# Top.net
KiCad netlist of a schematic drawn in Altium Designer
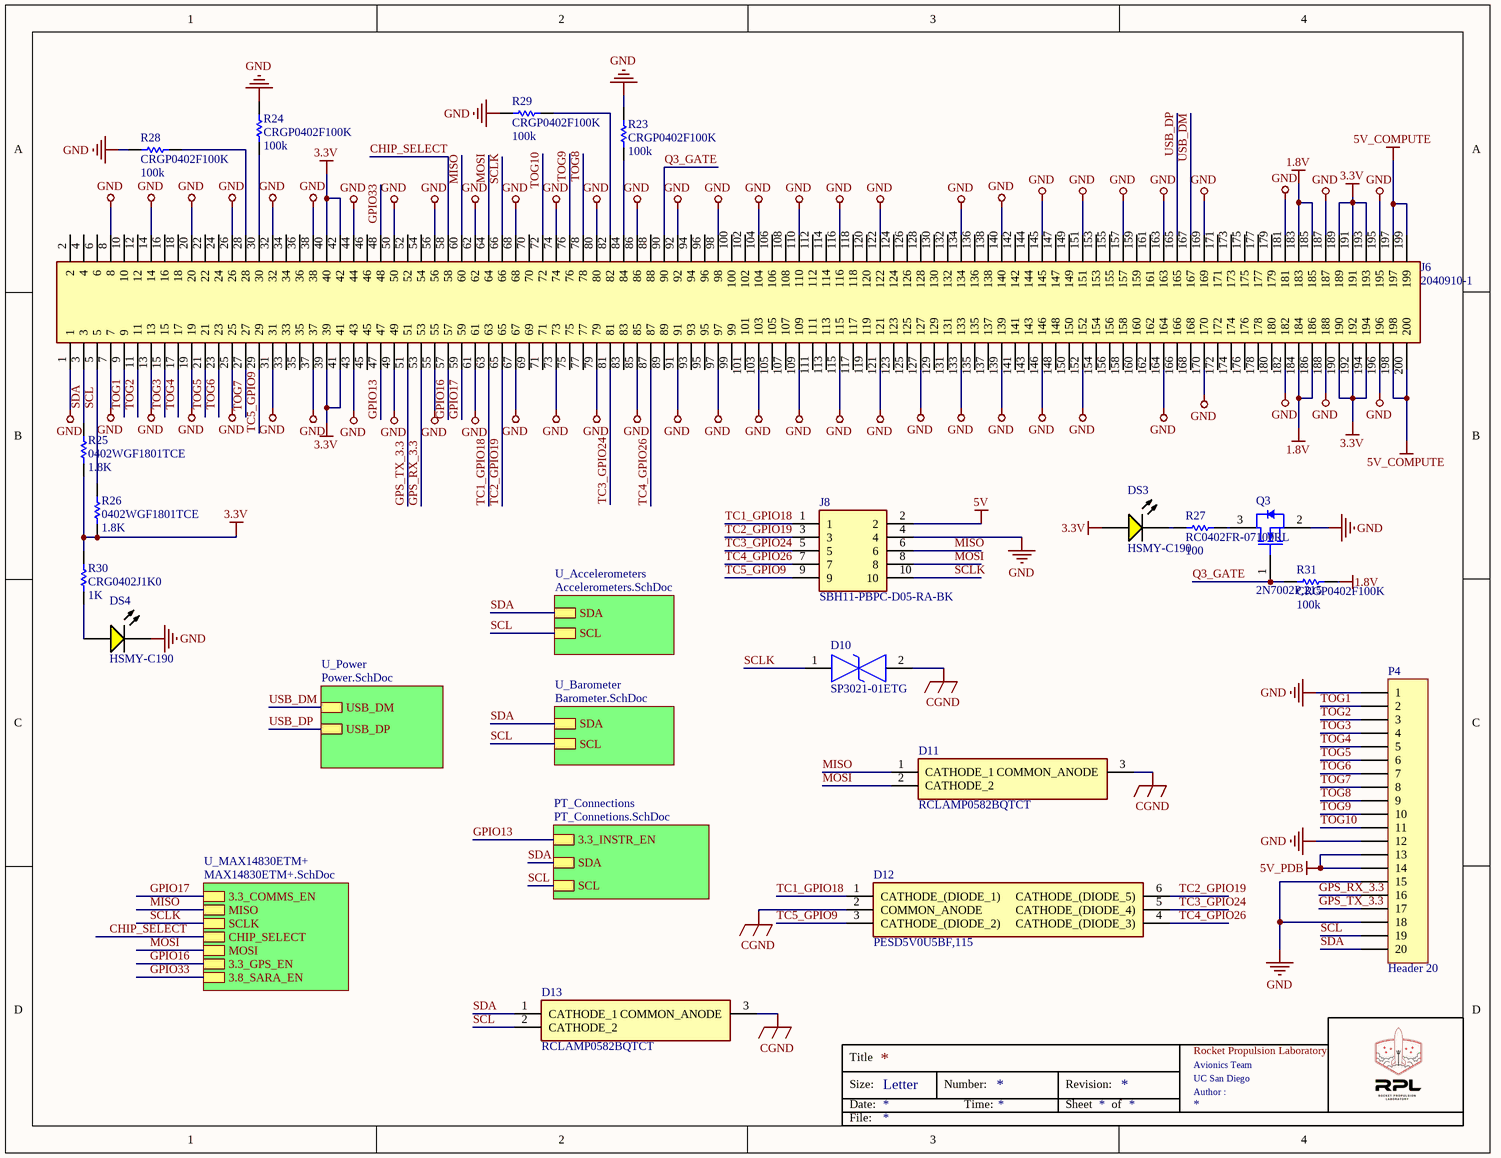
[diagram p0: Top.SchDoc]

(export (version "E")
  (design (tool "Eeschema 10.0.6"))
  (components
    (comp (ref "D10")
      (value "SP3021-01ETG")
      (footprint "PcbLib1:SP302101ETG")
      (description "TVS Diode (Bi-directional)")
      (fields (field (name "MOUSER PART NUMBER") "576-SP3021-01ETG"))
      (libsource (lib "*") (part "SP3021-01ETG"))
    )
    (comp (ref "D11")
      (value "RCLAMP0582BQTCT")
      (footprint "PcbLib1:SOT50P160X90-3N")
      (description "TVS Diode (Uni-directional)")
      (fields (field (name "MOUSER PART NUMBER") "947-RCLAMP0582BQTCT"))
      (libsource (lib "*") (part "RCLAMP0582BQTCT"))
    )
    (comp (ref "D12")
      (value "PESD5V0U5BF,115")
      (footprint "PcbLib1:PESD5V0U5BF115")
      (description "TVS Diode (Uni-directional)")
      (fields (field (name "MOUSER PART NUMBER") "771-PESD5V0U5BF,115"))
      (libsource (lib "*") (part "PESD5V0U5BF,115"))
    )
    (comp (ref "D13")
      (value "RCLAMP0582BQTCT")
      (footprint "PcbLib1:SOT50P160X90-3N")
      (description "TVS Diode (Uni-directional)")
      (fields (field (name "MOUSER PART NUMBER") "947-RCLAMP0582BQTCT"))
      (libsource (lib "*") (part "RCLAMP0582BQTCT"))
    )
    (comp (ref "DS3")
      (value "HSMY-C190")
      (footprint "AVAG-HSMX-C190_V")
      (description "LED Uni-Color Yellow, 65 mW, 20 mA, -40 to 85 degC, 2-Pin SMD, RoHS, Tape and Reel")
      (fields (field (name "TOLERANCE") "1%"))
      (libsource (lib "Altium Content Vault") (part "LED-YELLOW-AK-2"))
    )
    (comp (ref "DS4")
      (value "HSMY-C190")
      (footprint "AVAG-HSMX-C190_V")
      (description "LED Uni-Color Yellow, 65 mW, 20 mA, -40 to 85 degC, 2-Pin SMD, RoHS, Tape and Reel")
      (fields (field (name "TOLERANCE") "1%"))
      (libsource (lib "Altium Content Vault") (part "LED-YELLOW-AK-2"))
    )
    (comp (ref "J6")
      (value "2040910-1")
      (footprint "PcbLib1:20409101")
      (description "Connector")
      (fields (field (name "MOUSER PART NUMBER") "571-2040910-1"))
      (libsource (lib "*") (part "2040910-1"))
    )
    (comp (ref "J8")
      (value "SBH11-PBPC-D05-RA-BK")
      (footprint "PcbLib1:SHDRRA10W64P254_2X5_1270X910X880P")
      (description "Connector")
      (libsource (lib "*") (part "SBH11-PBPC-D05-RA-BK"))
    )
    (comp (ref "P4")
      (value "Header 20")
      (footprint "HDR1X20")
      (description "Header, 20-Pin")
      (fields (field (name "PUBLISHER") "Altium Limited"))
      (libsource (lib "Miscellaneous Connectors") (part "Header 20"))
    )
    (comp (ref "Q3")
      (value "2N7002P,215")
      (footprint "NXP-SOT23_L")
      (description "N-Channel Trench MOSFET, 60 V, 0.36 A, -55 to 150 degC, 3-Pin SOT23, Tape and Reel")
      (fields (field (name "MANUFACTURER") "NXP Semiconductors"))
      (libsource (lib "Altium Content Vault") (part "NXP-NMOS-GSD-3_B"))
    )
    (comp (ref "R23")
      (value "CRGP0402F100K")
      (footprint "0402")
      (description "Resistor")
      (fields (field (name "ALTIUM_VALUE") "100k") (field (name "PUBLISHER") "Altium Limited"))
      (libsource (lib "Miscellaneous Devices") (part "Res1"))
    )
    (comp (ref "R24")
      (value "CRGP0402F100K")
      (footprint "0402")
      (description "Resistor")
      (fields (field (name "ALTIUM_VALUE") "100k") (field (name "PUBLISHER") "Altium Limited"))
      (libsource (lib "Miscellaneous Devices") (part "Res1"))
    )
    (comp (ref "R25")
      (value "0402WGF1801TCE")
      (footprint "0402")
      (description "Resistor")
      (fields (field (name "ALTIUM_VALUE") "1.8K") (field (name "PUBLISHER") "Altium Limited"))
      (libsource (lib "Miscellaneous Devices") (part "Res1"))
    )
    (comp (ref "R26")
      (value "0402WGF1801TCE")
      (footprint "0402")
      (description "Resistor")
      (fields (field (name "ALTIUM_VALUE") "1.8K") (field (name "PUBLISHER") "Altium Limited"))
      (libsource (lib "Miscellaneous Devices") (part "Res1"))
    )
    (comp (ref "R27")
      (value "RC0402FR-07100RL")
      (footprint "RESC1005X40X25ML05T10")
      (fields (field (name "MANUFACTURER") "Yageo / Phycomp") (field (name "SPEC") "100"))
      (libsource (lib "Altium Content Vault") (part "RES"))
    )
    (comp (ref "R28")
      (value "CRGP0402F100K")
      (footprint "0402")
      (description "Resistor")
      (fields (field (name "ALTIUM_VALUE") "100k") (field (name "PUBLISHER") "Altium Limited"))
      (libsource (lib "Miscellaneous Devices") (part "Res1"))
    )
    (comp (ref "R29")
      (value "CRGP0402F100K")
      (footprint "0402")
      (description "Resistor")
      (fields (field (name "ALTIUM_VALUE") "100k") (field (name "PUBLISHER") "Altium Limited"))
      (libsource (lib "Miscellaneous Devices") (part "Res1"))
    )
    (comp (ref "R30")
      (value "CRG0402J1K0")
      (footprint "0402")
      (description "Resistor")
      (fields (field (name "ALTIUM_VALUE") "1K") (field (name "PUBLISHER") "Altium Limited"))
      (libsource (lib "Miscellaneous Devices") (part "Res1"))
    )
    (comp (ref "R31")
      (value "CRGP0402F100K")
      (footprint "0402")
      (description "Resistor")
      (fields (field (name "ALTIUM_VALUE") "100k") (field (name "PUBLISHER") "Altium Limited"))
      (libsource (lib "Miscellaneous Devices") (part "Res1"))
    )
  )
  (nets
    (net (code "1") (name "/CHIP_SELECT") (class "Default")
      (node (ref "J6") (pin "58") (pinfunction "58_58") (pintype "passive"))
    )
    (net (code "2") (name "/GPIO13") (class "Default")
      (node (ref "J6") (pin "47") (pinfunction "47_47") (pintype "passive"))
    )
    (net (code "3") (name "/GPIO16") (class "Default")
      (node (ref "J6") (pin "57") (pinfunction "57_57") (pintype "passive"))
    )
    (net (code "4") (name "/GPIO17") (class "Default")
      (node (ref "J6") (pin "59") (pinfunction "59_59") (pintype "passive"))
    )
    (net (code "5") (name "/GPIO33") (class "Default")
      (node (ref "J6") (pin "48") (pinfunction "48_48") (pintype "passive"))
    )
    (net (code "6") (name "/GPS_RX_3.3") (class "Default")
      (node (ref "J6") (pin "53") (pinfunction "53_53") (pintype "passive"))
      (node (ref "P4") (pin "16") (pinfunction "16_16") (pintype "passive"))
    )
    (net (code "7") (name "/GPS_TX_3.3") (class "Default")
      (node (ref "J6") (pin "51") (pinfunction "51_51") (pintype "passive"))
      (node (ref "P4") (pin "17") (pinfunction "17_17") (pintype "passive"))
    )
    (net (code "8") (name "/MISO") (class "Default")
      (node (ref "D11") (pin "1") (pinfunction "CATHODE_1_1") (pintype "passive"))
      (node (ref "J6") (pin "60") (pinfunction "60_60") (pintype "passive"))
      (node (ref "J8") (pin "6") (pinfunction "6_6") (pintype "passive"))
    )
    (net (code "9") (name "/MOSI") (class "Default")
      (node (ref "D11") (pin "2") (pinfunction "CATHODE_2_2") (pintype "passive"))
      (node (ref "J6") (pin "64") (pinfunction "64_64") (pintype "passive"))
      (node (ref "J8") (pin "8") (pinfunction "8_8") (pintype "passive"))
    )
    (net (code "10") (name "/Q3_GATE") (class "Default")
      (node (ref "J6") (pin "90") (pinfunction "90_90") (pintype "passive"))
      (node (ref "Q3") (pin "1") (pinfunction "G_1") (pintype "passive"))
      (node (ref "R31") (pin "1") (pinfunction "1_1") (pintype "passive"))
    )
    (net (code "11") (name "/SCL") (class "Default")
      (node (ref "D13") (pin "2") (pinfunction "CATHODE_2_2") (pintype "passive"))
      (node (ref "J6") (pin "5") (pinfunction "5_5") (pintype "passive"))
      (node (ref "P4") (pin "19") (pinfunction "19_19") (pintype "passive"))
      (node (ref "R26") (pin "2") (pinfunction "2_2") (pintype "passive"))
    )
    (net (code "12") (name "/SCLK") (class "Default")
      (node (ref "D10") (pin "1") (pinfunction "1_1") (pintype "passive"))
      (node (ref "J6") (pin "66") (pinfunction "66_66") (pintype "passive"))
      (node (ref "J8") (pin "10") (pinfunction "10_10") (pintype "passive"))
    )
    (net (code "13") (name "/SDA") (class "Default")
      (node (ref "D13") (pin "1") (pinfunction "CATHODE_1_1") (pintype "passive"))
      (node (ref "J6") (pin "3") (pinfunction "3_3") (pintype "passive"))
      (node (ref "P4") (pin "20") (pinfunction "20_20") (pintype "passive"))
      (node (ref "R25") (pin "2") (pinfunction "2_2") (pintype "passive"))
    )
    (net (code "14") (name "/TC1_GPIO18") (class "Default")
      (node (ref "D12") (pin "1") (pinfunction "CATHODE_(DIODE_1)_1") (pintype "passive"))
      (node (ref "J6") (pin "63") (pinfunction "63_63") (pintype "passive"))
      (node (ref "J8") (pin "1") (pinfunction "1_1") (pintype "passive"))
    )
    (net (code "15") (name "/TC2_GPIO19") (class "Default")
      (node (ref "D12") (pin "6") (pinfunction "CATHODE_(DIODE_5)_6") (pintype "passive"))
      (node (ref "J6") (pin "65") (pinfunction "65_65") (pintype "passive"))
      (node (ref "J8") (pin "3") (pinfunction "3_3") (pintype "passive"))
    )
    (net (code "16") (name "/TC3_GPIO24") (class "Default")
      (node (ref "D12") (pin "5") (pinfunction "CATHODE_(DIODE_4)_5") (pintype "passive"))
      (node (ref "J6") (pin "81") (pinfunction "81_81") (pintype "passive"))
      (node (ref "J8") (pin "5") (pinfunction "5_5") (pintype "passive"))
    )
    (net (code "17") (name "/TC4_GPIO26") (class "Default")
      (node (ref "D12") (pin "4") (pinfunction "CATHODE_(DIODE_3)_4") (pintype "passive"))
      (node (ref "J6") (pin "87") (pinfunction "87_87") (pintype "passive"))
      (node (ref "J8") (pin "7") (pinfunction "7_7") (pintype "passive"))
    )
    (net (code "18") (name "/TC5_GPIO9") (class "Default")
      (node (ref "D12") (pin "3") (pinfunction "CATHODE_(DIODE_2)_3") (pintype "passive"))
      (node (ref "J6") (pin "29") (pinfunction "29_29") (pintype "passive"))
      (node (ref "J8") (pin "9") (pinfunction "9_9") (pintype "passive"))
    )
    (net (code "19") (name "/TOG1") (class "Default")
      (node (ref "J6") (pin "9") (pinfunction "9_9") (pintype "passive"))
      (node (ref "P4") (pin "2") (pinfunction "2_2") (pintype "passive"))
    )
    (net (code "20") (name "/TOG2") (class "Default")
      (node (ref "J6") (pin "11") (pinfunction "11_11") (pintype "passive"))
      (node (ref "P4") (pin "3") (pinfunction "3_3") (pintype "passive"))
    )
    (net (code "21") (name "/TOG3") (class "Default")
      (node (ref "J6") (pin "15") (pinfunction "15_15") (pintype "passive"))
      (node (ref "P4") (pin "4") (pinfunction "4_4") (pintype "passive"))
    )
    (net (code "22") (name "/TOG4") (class "Default")
      (node (ref "J6") (pin "17") (pinfunction "17_17") (pintype "passive"))
      (node (ref "P4") (pin "5") (pinfunction "5_5") (pintype "passive"))
    )
    (net (code "23") (name "/TOG5") (class "Default")
      (node (ref "J6") (pin "21") (pinfunction "21_21") (pintype "passive"))
      (node (ref "P4") (pin "6") (pinfunction "6_6") (pintype "passive"))
    )
    (net (code "24") (name "/TOG6") (class "Default")
      (node (ref "J6") (pin "23") (pinfunction "23_23") (pintype "passive"))
      (node (ref "P4") (pin "7") (pinfunction "7_7") (pintype "passive"))
    )
    (net (code "25") (name "/TOG7") (class "Default")
      (node (ref "J6") (pin "27") (pinfunction "27_27") (pintype "passive"))
      (node (ref "P4") (pin "8") (pinfunction "8_8") (pintype "passive"))
    )
    (net (code "26") (name "/TOG8") (class "Default")
      (node (ref "J6") (pin "78") (pinfunction "78_78") (pintype "passive"))
      (node (ref "P4") (pin "9") (pinfunction "9_9") (pintype "passive"))
    )
    (net (code "27") (name "/TOG9") (class "Default")
      (node (ref "J6") (pin "76") (pinfunction "76_76") (pintype "passive"))
      (node (ref "P4") (pin "10") (pinfunction "10_10") (pintype "passive"))
    )
    (net (code "28") (name "/TOG10") (class "Default")
      (node (ref "J6") (pin "72") (pinfunction "72_72") (pintype "passive"))
      (node (ref "P4") (pin "11") (pinfunction "11_11") (pintype "passive"))
    )
    (net (code "29") (name "/USB_DM") (class "Default")
      (node (ref "J6") (pin "167") (pinfunction "167_167") (pintype "passive"))
    )
    (net (code "30") (name "/USB_DP") (class "Default")
      (node (ref "J6") (pin "165") (pinfunction "165_165") (pintype "passive"))
    )
    (net (code "31") (name "1.8V") (class "Default")
      (node (ref "J6") (pin "183") (pinfunction "183_183") (pintype "passive"))
      (node (ref "J6") (pin "184") (pinfunction "184_184") (pintype "passive"))
      (node (ref "J6") (pin "185") (pinfunction "185_185") (pintype "passive"))
      (node (ref "J6") (pin "186") (pinfunction "186_186") (pintype "passive"))
      (node (ref "R31") (pin "2") (pinfunction "2_2") (pintype "passive"))
    )
    (net (code "32") (name "3.3V") (class "Default")
      (node (ref "DS3") (pin "1") (pinfunction "A_1") (pintype "passive"))
      (node (ref "J6") (pin "189") (pinfunction "189_189") (pintype "passive"))
      (node (ref "J6") (pin "190") (pinfunction "190_190") (pintype "passive"))
      (node (ref "J6") (pin "191") (pinfunction "191_191") (pintype "passive"))
      (node (ref "J6") (pin "192") (pinfunction "192_192") (pintype "passive"))
      (node (ref "J6") (pin "193") (pinfunction "193_193") (pintype "passive"))
      (node (ref "J6") (pin "194") (pinfunction "194_194") (pintype "passive"))
      (node (ref "J6") (pin "39") (pinfunction "39_39") (pintype "passive"))
      (node (ref "J6") (pin "40") (pinfunction "40_40") (pintype "passive"))
      (node (ref "J6") (pin "41") (pinfunction "41_41") (pintype "passive"))
      (node (ref "J6") (pin "42") (pinfunction "42_42") (pintype "passive"))
      (node (ref "R25") (pin "1") (pinfunction "1_1") (pintype "passive"))
      (node (ref "R26") (pin "1") (pinfunction "1_1") (pintype "passive"))
      (node (ref "R30") (pin "1") (pinfunction "1_1") (pintype "passive"))
    )
    (net (code "33") (name "5V") (class "Default")
      (node (ref "J8") (pin "2") (pinfunction "2_2") (pintype "passive"))
    )
    (net (code "34") (name "5V_COMPUTE") (class "Default")
      (node (ref "J6") (pin "197") (pinfunction "197_197") (pintype "passive"))
      (node (ref "J6") (pin "198") (pinfunction "198_198") (pintype "passive"))
      (node (ref "J6") (pin "199") (pinfunction "199_199") (pintype "passive"))
      (node (ref "J6") (pin "200") (pinfunction "200_200") (pintype "passive"))
    )
    (net (code "35") (name "5V_PDB") (class "Default")
      (node (ref "P4") (pin "13") (pinfunction "13_13") (pintype "passive"))
      (node (ref "P4") (pin "14") (pinfunction "14_14") (pintype "passive"))
    )
    (net (code "36") (name "CGND") (class "Default")
      (node (ref "D10") (pin "2") (pinfunction "2_2") (pintype "passive"))
      (node (ref "D11") (pin "3") (pinfunction "COMMON_ANODE_3") (pintype "passive"))
      (node (ref "D12") (pin "2") (pinfunction "COMMON_ANODE_2") (pintype "passive"))
      (node (ref "D13") (pin "3") (pinfunction "COMMON_ANODE_3") (pintype "passive"))
    )
    (net (code "37") (name "GND") (class "Default")
      (node (ref "DS4") (pin "2") (pinfunction "K_2") (pintype "passive"))
      (node (ref "J6") (pin "1") (pinfunction "1_1") (pintype "passive"))
      (node (ref "J6") (pin "103") (pinfunction "103_103") (pintype "passive"))
      (node (ref "J6") (pin "104") (pinfunction "104_104") (pintype "passive"))
      (node (ref "J6") (pin "109") (pinfunction "109_109") (pintype "passive"))
      (node (ref "J6") (pin "110") (pinfunction "110_110") (pintype "passive"))
      (node (ref "J6") (pin "115") (pinfunction "115_115") (pintype "passive"))
      (node (ref "J6") (pin "116") (pinfunction "116_116") (pintype "passive"))
      (node (ref "J6") (pin "121") (pinfunction "121_121") (pintype "passive"))
      (node (ref "J6") (pin "122") (pinfunction "122_122") (pintype "passive"))
      (node (ref "J6") (pin "127") (pinfunction "127_127") (pintype "passive"))
      (node (ref "J6") (pin "13") (pinfunction "13_13") (pintype "passive"))
      (node (ref "J6") (pin "133") (pinfunction "133_133") (pintype "passive"))
      (node (ref "J6") (pin "134") (pinfunction "134_134") (pintype "passive"))
      (node (ref "J6") (pin "139") (pinfunction "139_139") (pintype "passive"))
      (node (ref "J6") (pin "14") (pinfunction "14_14") (pintype "passive"))
      (node (ref "J6") (pin "140") (pinfunction "140_140") (pintype "passive"))
      (node (ref "J6") (pin "145") (pinfunction "145_145") (pintype "passive"))
      (node (ref "J6") (pin "146") (pinfunction "146_146") (pintype "passive"))
      (node (ref "J6") (pin "151") (pinfunction "151_151") (pintype "passive"))
      (node (ref "J6") (pin "152") (pinfunction "152_152") (pintype "passive"))
      (node (ref "J6") (pin "157") (pinfunction "157_157") (pintype "passive"))
      (node (ref "J6") (pin "163") (pinfunction "163_163") (pintype "passive"))
      (node (ref "J6") (pin "164") (pinfunction "164_164") (pintype "passive"))
      (node (ref "J6") (pin "169") (pinfunction "169_169") (pintype "passive"))
      (node (ref "J6") (pin "170") (pinfunction "170_170") (pintype "passive"))
      (node (ref "J6") (pin "181") (pinfunction "181_181") (pintype "passive"))
      (node (ref "J6") (pin "182") (pinfunction "182_182") (pintype "passive"))
      (node (ref "J6") (pin "187") (pinfunction "187_187") (pintype "passive"))
      (node (ref "J6") (pin "188") (pinfunction "188_188") (pintype "passive"))
      (node (ref "J6") (pin "19") (pinfunction "19_19") (pintype "passive"))
      (node (ref "J6") (pin "195") (pinfunction "195_195") (pintype "passive"))
      (node (ref "J6") (pin "196") (pinfunction "196_196") (pintype "passive"))
      (node (ref "J6") (pin "20") (pinfunction "20_20") (pintype "passive"))
      (node (ref "J6") (pin "25") (pinfunction "25_25") (pintype "passive"))
      (node (ref "J6") (pin "26") (pinfunction "26_26") (pintype "passive"))
      (node (ref "J6") (pin "31") (pinfunction "31_31") (pintype "passive"))
      (node (ref "J6") (pin "32") (pinfunction "32_32") (pintype "passive"))
      (node (ref "J6") (pin "37") (pinfunction "37_37") (pintype "passive"))
      (node (ref "J6") (pin "38") (pinfunction "38_38") (pintype "passive"))
      (node (ref "J6") (pin "43") (pinfunction "43_43") (pintype "passive"))
      (node (ref "J6") (pin "44") (pinfunction "44_44") (pintype "passive"))
      (node (ref "J6") (pin "49") (pinfunction "49_49") (pintype "passive"))
      (node (ref "J6") (pin "50") (pinfunction "50_50") (pintype "passive"))
      (node (ref "J6") (pin "55") (pinfunction "55_55") (pintype "passive"))
      (node (ref "J6") (pin "56") (pinfunction "56_56") (pintype "passive"))
      (node (ref "J6") (pin "61") (pinfunction "61_61") (pintype "passive"))
      (node (ref "J6") (pin "62") (pinfunction "62_62") (pintype "passive"))
      (node (ref "J6") (pin "67") (pinfunction "67_67") (pintype "passive"))
      (node (ref "J6") (pin "68") (pinfunction "68_68") (pintype "passive"))
      (node (ref "J6") (pin "7") (pinfunction "7_7") (pintype "passive"))
      (node (ref "J6") (pin "73") (pinfunction "73_73") (pintype "passive"))
      (node (ref "J6") (pin "74") (pinfunction "74_74") (pintype "passive"))
      (node (ref "J6") (pin "79") (pinfunction "79_79") (pintype "passive"))
      (node (ref "J6") (pin "8") (pinfunction "8_8") (pintype "passive"))
      (node (ref "J6") (pin "80") (pinfunction "80_80") (pintype "passive"))
      (node (ref "J6") (pin "85") (pinfunction "85_85") (pintype "passive"))
      (node (ref "J6") (pin "86") (pinfunction "86_86") (pintype "passive"))
      (node (ref "J6") (pin "91") (pinfunction "91_91") (pintype "passive"))
      (node (ref "J6") (pin "92") (pinfunction "92_92") (pintype "passive"))
      (node (ref "J6") (pin "97") (pinfunction "97_97") (pintype "passive"))
      (node (ref "J6") (pin "98") (pinfunction "98_98") (pintype "passive"))
      (node (ref "J8") (pin "4") (pinfunction "4_4") (pintype "passive"))
      (node (ref "P4") (pin "1") (pinfunction "1_1") (pintype "passive"))
      (node (ref "P4") (pin "12") (pinfunction "12_12") (pintype "passive"))
      (node (ref "P4") (pin "15") (pinfunction "15_15") (pintype "passive"))
      (node (ref "P4") (pin "18") (pinfunction "18_18") (pintype "passive"))
      (node (ref "Q3") (pin "2") (pinfunction "S_2") (pintype "passive"))
      (node (ref "R23") (pin "2") (pinfunction "2_2") (pintype "passive"))
      (node (ref "R24") (pin "2") (pinfunction "2_2") (pintype "passive"))
      (node (ref "R28") (pin "2") (pinfunction "2_2") (pintype "passive"))
      (node (ref "R29") (pin "2") (pinfunction "2_2") (pintype "passive"))
    )
    (net (code "38") (name "Net-(DS3-K)") (class "Default")
      (node (ref "DS3") (pin "2") (pinfunction "K_2") (pintype "passive"))
      (node (ref "R27") (pin "2") (pinfunction "2_2") (pintype "passive"))
    )
    (net (code "39") (name "Net-(DS4-A)") (class "Default")
      (node (ref "DS4") (pin "1") (pinfunction "A_1") (pintype "passive"))
      (node (ref "R30") (pin "2") (pinfunction "2_2") (pintype "passive"))
    )
    (net (code "40") (name "Net-(J6-Pad28)") (class "Default")
      (node (ref "J6") (pin "28") (pinfunction "28_28") (pintype "passive"))
      (node (ref "R28") (pin "1") (pinfunction "1_1") (pintype "passive"))
    )
    (net (code "41") (name "Net-(J6-Pad30)") (class "Default")
      (node (ref "J6") (pin "30") (pinfunction "30_30") (pintype "passive"))
      (node (ref "R24") (pin "1") (pinfunction "1_1") (pintype "passive"))
    )
    (net (code "42") (name "Net-(J6-Pad82)") (class "Default")
      (node (ref "J6") (pin "82") (pinfunction "82_82") (pintype "passive"))
      (node (ref "R29") (pin "1") (pinfunction "1_1") (pintype "passive"))
    )
    (net (code "43") (name "Net-(J6-Pad84)") (class "Default")
      (node (ref "J6") (pin "84") (pinfunction "84_84") (pintype "passive"))
      (node (ref "R23") (pin "1") (pinfunction "1_1") (pintype "passive"))
    )
    (net (code "44") (name "Net-(Q3-D)") (class "Default")
      (node (ref "Q3") (pin "3") (pinfunction "D_3") (pintype "passive"))
      (node (ref "R27") (pin "1") (pinfunction "1_1") (pintype "passive"))
    )
    (net (code "45") (name "unconnected-(J6-Pad2)") (class "Default")
      (node (ref "J6") (pin "2") (pinfunction "2_2") (pintype "passive"))
    )
    (net (code "46") (name "unconnected-(J6-Pad4)") (class "Default")
      (node (ref "J6") (pin "4") (pinfunction "4_4") (pintype "passive"))
    )
    (net (code "47") (name "unconnected-(J6-Pad6)") (class "Default")
      (node (ref "J6") (pin "6") (pinfunction "6_6") (pintype "passive"))
    )
    (net (code "48") (name "unconnected-(J6-Pad10)") (class "Default")
      (node (ref "J6") (pin "10") (pinfunction "10_10") (pintype "passive"))
    )
    (net (code "49") (name "unconnected-(J6-Pad12)") (class "Default")
      (node (ref "J6") (pin "12") (pinfunction "12_12") (pintype "passive"))
    )
    (net (code "50") (name "unconnected-(J6-Pad16)") (class "Default")
      (node (ref "J6") (pin "16") (pinfunction "16_16") (pintype "passive"))
    )
    (net (code "51") (name "unconnected-(J6-Pad18)") (class "Default")
      (node (ref "J6") (pin "18") (pinfunction "18_18") (pintype "passive"))
    )
    (net (code "52") (name "unconnected-(J6-Pad22)") (class "Default")
      (node (ref "J6") (pin "22") (pinfunction "22_22") (pintype "passive"))
    )
    (net (code "53") (name "unconnected-(J6-Pad24)") (class "Default")
      (node (ref "J6") (pin "24") (pinfunction "24_24") (pintype "passive"))
    )
    (net (code "54") (name "unconnected-(J6-Pad33)") (class "Default")
      (node (ref "J6") (pin "33") (pinfunction "33_33") (pintype "passive"))
    )
    (net (code "55") (name "unconnected-(J6-Pad34)") (class "Default")
      (node (ref "J6") (pin "34") (pinfunction "34_34") (pintype "passive"))
    )
    (net (code "56") (name "unconnected-(J6-Pad35)") (class "Default")
      (node (ref "J6") (pin "35") (pinfunction "35_35") (pintype "passive"))
    )
    (net (code "57") (name "unconnected-(J6-Pad36)") (class "Default")
      (node (ref "J6") (pin "36") (pinfunction "36_36") (pintype "passive"))
    )
    (net (code "58") (name "unconnected-(J6-Pad45)") (class "Default")
      (node (ref "J6") (pin "45") (pinfunction "45_45") (pintype "passive"))
    )
    (net (code "59") (name "unconnected-(J6-Pad46)") (class "Default")
      (node (ref "J6") (pin "46") (pinfunction "46_46") (pintype "passive"))
    )
    (net (code "60") (name "unconnected-(J6-Pad52)") (class "Default")
      (node (ref "J6") (pin "52") (pinfunction "52_52") (pintype "passive"))
    )
    (net (code "61") (name "unconnected-(J6-Pad54)") (class "Default")
      (node (ref "J6") (pin "54") (pinfunction "54_54") (pintype "passive"))
    )
    (net (code "62") (name "unconnected-(J6-Pad69)") (class "Default")
      (node (ref "J6") (pin "69") (pinfunction "69_69") (pintype "passive"))
    )
    (net (code "63") (name "unconnected-(J6-Pad70)") (class "Default")
      (node (ref "J6") (pin "70") (pinfunction "70_70") (pintype "passive"))
    )
    (net (code "64") (name "unconnected-(J6-Pad71)") (class "Default")
      (node (ref "J6") (pin "71") (pinfunction "71_71") (pintype "passive"))
    )
    (net (code "65") (name "unconnected-(J6-Pad75)") (class "Default")
      (node (ref "J6") (pin "75") (pinfunction "75_75") (pintype "passive"))
    )
    (net (code "66") (name "unconnected-(J6-Pad77)") (class "Default")
      (node (ref "J6") (pin "77") (pinfunction "77_77") (pintype "passive"))
    )
    (net (code "67") (name "unconnected-(J6-Pad83)") (class "Default")
      (node (ref "J6") (pin "83") (pinfunction "83_83") (pintype "passive"))
    )
    (net (code "68") (name "unconnected-(J6-Pad88)") (class "Default")
      (node (ref "J6") (pin "88") (pinfunction "88_88") (pintype "passive"))
    )
    (net (code "69") (name "unconnected-(J6-Pad89)") (class "Default")
      (node (ref "J6") (pin "89") (pinfunction "89_89") (pintype "passive"))
    )
    (net (code "70") (name "unconnected-(J6-Pad93)") (class "Default")
      (node (ref "J6") (pin "93") (pinfunction "93_93") (pintype "passive"))
    )
    (net (code "71") (name "unconnected-(J6-Pad94)") (class "Default")
      (node (ref "J6") (pin "94") (pinfunction "94_94") (pintype "passive"))
    )
    (net (code "72") (name "unconnected-(J6-Pad95)") (class "Default")
      (node (ref "J6") (pin "95") (pinfunction "95_95") (pintype "passive"))
    )
    (net (code "73") (name "unconnected-(J6-Pad96)") (class "Default")
      (node (ref "J6") (pin "96") (pinfunction "96_96") (pintype "passive"))
    )
    (net (code "74") (name "unconnected-(J6-Pad99)") (class "Default")
      (node (ref "J6") (pin "99") (pinfunction "99_99") (pintype "passive"))
    )
    (net (code "75") (name "unconnected-(J6-Pad100)") (class "Default")
      (node (ref "J6") (pin "100") (pinfunction "100_100") (pintype "passive"))
    )
    (net (code "76") (name "unconnected-(J6-Pad101)") (class "Default")
      (node (ref "J6") (pin "101") (pinfunction "101_101") (pintype "passive"))
    )
    (net (code "77") (name "unconnected-(J6-Pad102)") (class "Default")
      (node (ref "J6") (pin "102") (pinfunction "102_102") (pintype "passive"))
    )
    (net (code "78") (name "unconnected-(J6-Pad105)") (class "Default")
      (node (ref "J6") (pin "105") (pinfunction "105_105") (pintype "passive"))
    )
    (net (code "79") (name "unconnected-(J6-Pad106)") (class "Default")
      (node (ref "J6") (pin "106") (pinfunction "106_106") (pintype "passive"))
    )
    (net (code "80") (name "unconnected-(J6-Pad107)") (class "Default")
      (node (ref "J6") (pin "107") (pinfunction "107_107") (pintype "passive"))
    )
    (net (code "81") (name "unconnected-(J6-Pad108)") (class "Default")
      (node (ref "J6") (pin "108") (pinfunction "108_108") (pintype "passive"))
    )
    (net (code "82") (name "unconnected-(J6-Pad111)") (class "Default")
      (node (ref "J6") (pin "111") (pinfunction "111_111") (pintype "passive"))
    )
    (net (code "83") (name "unconnected-(J6-Pad112)") (class "Default")
      (node (ref "J6") (pin "112") (pinfunction "112_112") (pintype "passive"))
    )
    (net (code "84") (name "unconnected-(J6-Pad113)") (class "Default")
      (node (ref "J6") (pin "113") (pinfunction "113_113") (pintype "passive"))
    )
    (net (code "85") (name "unconnected-(J6-Pad114)") (class "Default")
      (node (ref "J6") (pin "114") (pinfunction "114_114") (pintype "passive"))
    )
    (net (code "86") (name "unconnected-(J6-Pad117)") (class "Default")
      (node (ref "J6") (pin "117") (pinfunction "117_117") (pintype "passive"))
    )
    (net (code "87") (name "unconnected-(J6-Pad118)") (class "Default")
      (node (ref "J6") (pin "118") (pinfunction "118_118") (pintype "passive"))
    )
    (net (code "88") (name "unconnected-(J6-Pad119)") (class "Default")
      (node (ref "J6") (pin "119") (pinfunction "119_119") (pintype "passive"))
    )
    (net (code "89") (name "unconnected-(J6-Pad120)") (class "Default")
      (node (ref "J6") (pin "120") (pinfunction "120_120") (pintype "passive"))
    )
    (net (code "90") (name "unconnected-(J6-Pad123)") (class "Default")
      (node (ref "J6") (pin "123") (pinfunction "123_123") (pintype "passive"))
    )
    (net (code "91") (name "unconnected-(J6-Pad124)") (class "Default")
      (node (ref "J6") (pin "124") (pinfunction "124_124") (pintype "passive"))
    )
    (net (code "92") (name "unconnected-(J6-Pad125)") (class "Default")
      (node (ref "J6") (pin "125") (pinfunction "125_125") (pintype "passive"))
    )
    (net (code "93") (name "unconnected-(J6-Pad126)") (class "Default")
      (node (ref "J6") (pin "126") (pinfunction "126_126") (pintype "passive"))
    )
    (net (code "94") (name "unconnected-(J6-Pad128)") (class "Default")
      (node (ref "J6") (pin "128") (pinfunction "128_128") (pintype "passive"))
    )
    (net (code "95") (name "unconnected-(J6-Pad129)") (class "Default")
      (node (ref "J6") (pin "129") (pinfunction "129_129") (pintype "passive"))
    )
    (net (code "96") (name "unconnected-(J6-Pad130)") (class "Default")
      (node (ref "J6") (pin "130") (pinfunction "130_130") (pintype "passive"))
    )
    (net (code "97") (name "unconnected-(J6-Pad131)") (class "Default")
      (node (ref "J6") (pin "131") (pinfunction "131_131") (pintype "passive"))
    )
    (net (code "98") (name "unconnected-(J6-Pad132)") (class "Default")
      (node (ref "J6") (pin "132") (pinfunction "132_132") (pintype "passive"))
    )
    (net (code "99") (name "unconnected-(J6-Pad135)") (class "Default")
      (node (ref "J6") (pin "135") (pinfunction "135_135") (pintype "passive"))
    )
    (net (code "100") (name "unconnected-(J6-Pad136)") (class "Default")
      (node (ref "J6") (pin "136") (pinfunction "136_136") (pintype "passive"))
    )
    (net (code "101") (name "unconnected-(J6-Pad137)") (class "Default")
      (node (ref "J6") (pin "137") (pinfunction "137_137") (pintype "passive"))
    )
    (net (code "102") (name "unconnected-(J6-Pad138)") (class "Default")
      (node (ref "J6") (pin "138") (pinfunction "138_138") (pintype "passive"))
    )
    (net (code "103") (name "unconnected-(J6-Pad141)") (class "Default")
      (node (ref "J6") (pin "141") (pinfunction "141_141") (pintype "passive"))
    )
    (net (code "104") (name "unconnected-(J6-Pad142)") (class "Default")
      (node (ref "J6") (pin "142") (pinfunction "142_142") (pintype "passive"))
    )
    (net (code "105") (name "unconnected-(J6-Pad143)") (class "Default")
      (node (ref "J6") (pin "143") (pinfunction "143_143") (pintype "passive"))
    )
    (net (code "106") (name "unconnected-(J6-Pad144)") (class "Default")
      (node (ref "J6") (pin "144") (pinfunction "144_144") (pintype "passive"))
    )
    (net (code "107") (name "unconnected-(J6-Pad147)") (class "Default")
      (node (ref "J6") (pin "147") (pinfunction "147_147") (pintype "passive"))
    )
    (net (code "108") (name "unconnected-(J6-Pad148)") (class "Default")
      (node (ref "J6") (pin "148") (pinfunction "148_148") (pintype "passive"))
    )
    (net (code "109") (name "unconnected-(J6-Pad149)") (class "Default")
      (node (ref "J6") (pin "149") (pinfunction "149_149") (pintype "passive"))
    )
    (net (code "110") (name "unconnected-(J6-Pad150)") (class "Default")
      (node (ref "J6") (pin "150") (pinfunction "150_150") (pintype "passive"))
    )
    (net (code "111") (name "unconnected-(J6-Pad153)") (class "Default")
      (node (ref "J6") (pin "153") (pinfunction "153_153") (pintype "passive"))
    )
    (net (code "112") (name "unconnected-(J6-Pad154)") (class "Default")
      (node (ref "J6") (pin "154") (pinfunction "154_154") (pintype "passive"))
    )
    (net (code "113") (name "unconnected-(J6-Pad155)") (class "Default")
      (node (ref "J6") (pin "155") (pinfunction "155_155") (pintype "passive"))
    )
    (net (code "114") (name "unconnected-(J6-Pad156)") (class "Default")
      (node (ref "J6") (pin "156") (pinfunction "156_156") (pintype "passive"))
    )
    (net (code "115") (name "unconnected-(J6-Pad158)") (class "Default")
      (node (ref "J6") (pin "158") (pinfunction "158_158") (pintype "passive"))
    )
    (net (code "116") (name "unconnected-(J6-Pad159)") (class "Default")
      (node (ref "J6") (pin "159") (pinfunction "159_159") (pintype "passive"))
    )
    (net (code "117") (name "unconnected-(J6-Pad160)") (class "Default")
      (node (ref "J6") (pin "160") (pinfunction "160_160") (pintype "passive"))
    )
    (net (code "118") (name "unconnected-(J6-Pad161)") (class "Default")
      (node (ref "J6") (pin "161") (pinfunction "161_161") (pintype "passive"))
    )
    (net (code "119") (name "unconnected-(J6-Pad162)") (class "Default")
      (node (ref "J6") (pin "162") (pinfunction "162_162") (pintype "passive"))
    )
    (net (code "120") (name "unconnected-(J6-Pad166)") (class "Default")
      (node (ref "J6") (pin "166") (pinfunction "166_166") (pintype "passive"))
    )
    (net (code "121") (name "unconnected-(J6-Pad168)") (class "Default")
      (node (ref "J6") (pin "168") (pinfunction "168_168") (pintype "passive"))
    )
    (net (code "122") (name "unconnected-(J6-Pad171)") (class "Default")
      (node (ref "J6") (pin "171") (pinfunction "171_171") (pintype "passive"))
    )
    (net (code "123") (name "unconnected-(J6-Pad172)") (class "Default")
      (node (ref "J6") (pin "172") (pinfunction "172_172") (pintype "passive"))
    )
    (net (code "124") (name "unconnected-(J6-Pad173)") (class "Default")
      (node (ref "J6") (pin "173") (pinfunction "173_173") (pintype "passive"))
    )
    (net (code "125") (name "unconnected-(J6-Pad174)") (class "Default")
      (node (ref "J6") (pin "174") (pinfunction "174_174") (pintype "passive"))
    )
    (net (code "126") (name "unconnected-(J6-Pad175)") (class "Default")
      (node (ref "J6") (pin "175") (pinfunction "175_175") (pintype "passive"))
    )
    (net (code "127") (name "unconnected-(J6-Pad176)") (class "Default")
      (node (ref "J6") (pin "176") (pinfunction "176_176") (pintype "passive"))
    )
    (net (code "128") (name "unconnected-(J6-Pad177)") (class "Default")
      (node (ref "J6") (pin "177") (pinfunction "177_177") (pintype "passive"))
    )
    (net (code "129") (name "unconnected-(J6-Pad178)") (class "Default")
      (node (ref "J6") (pin "178") (pinfunction "178_178") (pintype "passive"))
    )
    (net (code "130") (name "unconnected-(J6-Pad179)") (class "Default")
      (node (ref "J6") (pin "179") (pinfunction "179_179") (pintype "passive"))
    )
    (net (code "131") (name "unconnected-(J6-Pad180)") (class "Default")
      (node (ref "J6") (pin "180") (pinfunction "180_180") (pintype "passive"))
    )
  )
)
